# vic-20-mem-board.net
KiCad netlist of a schematic drawn in EAGLE
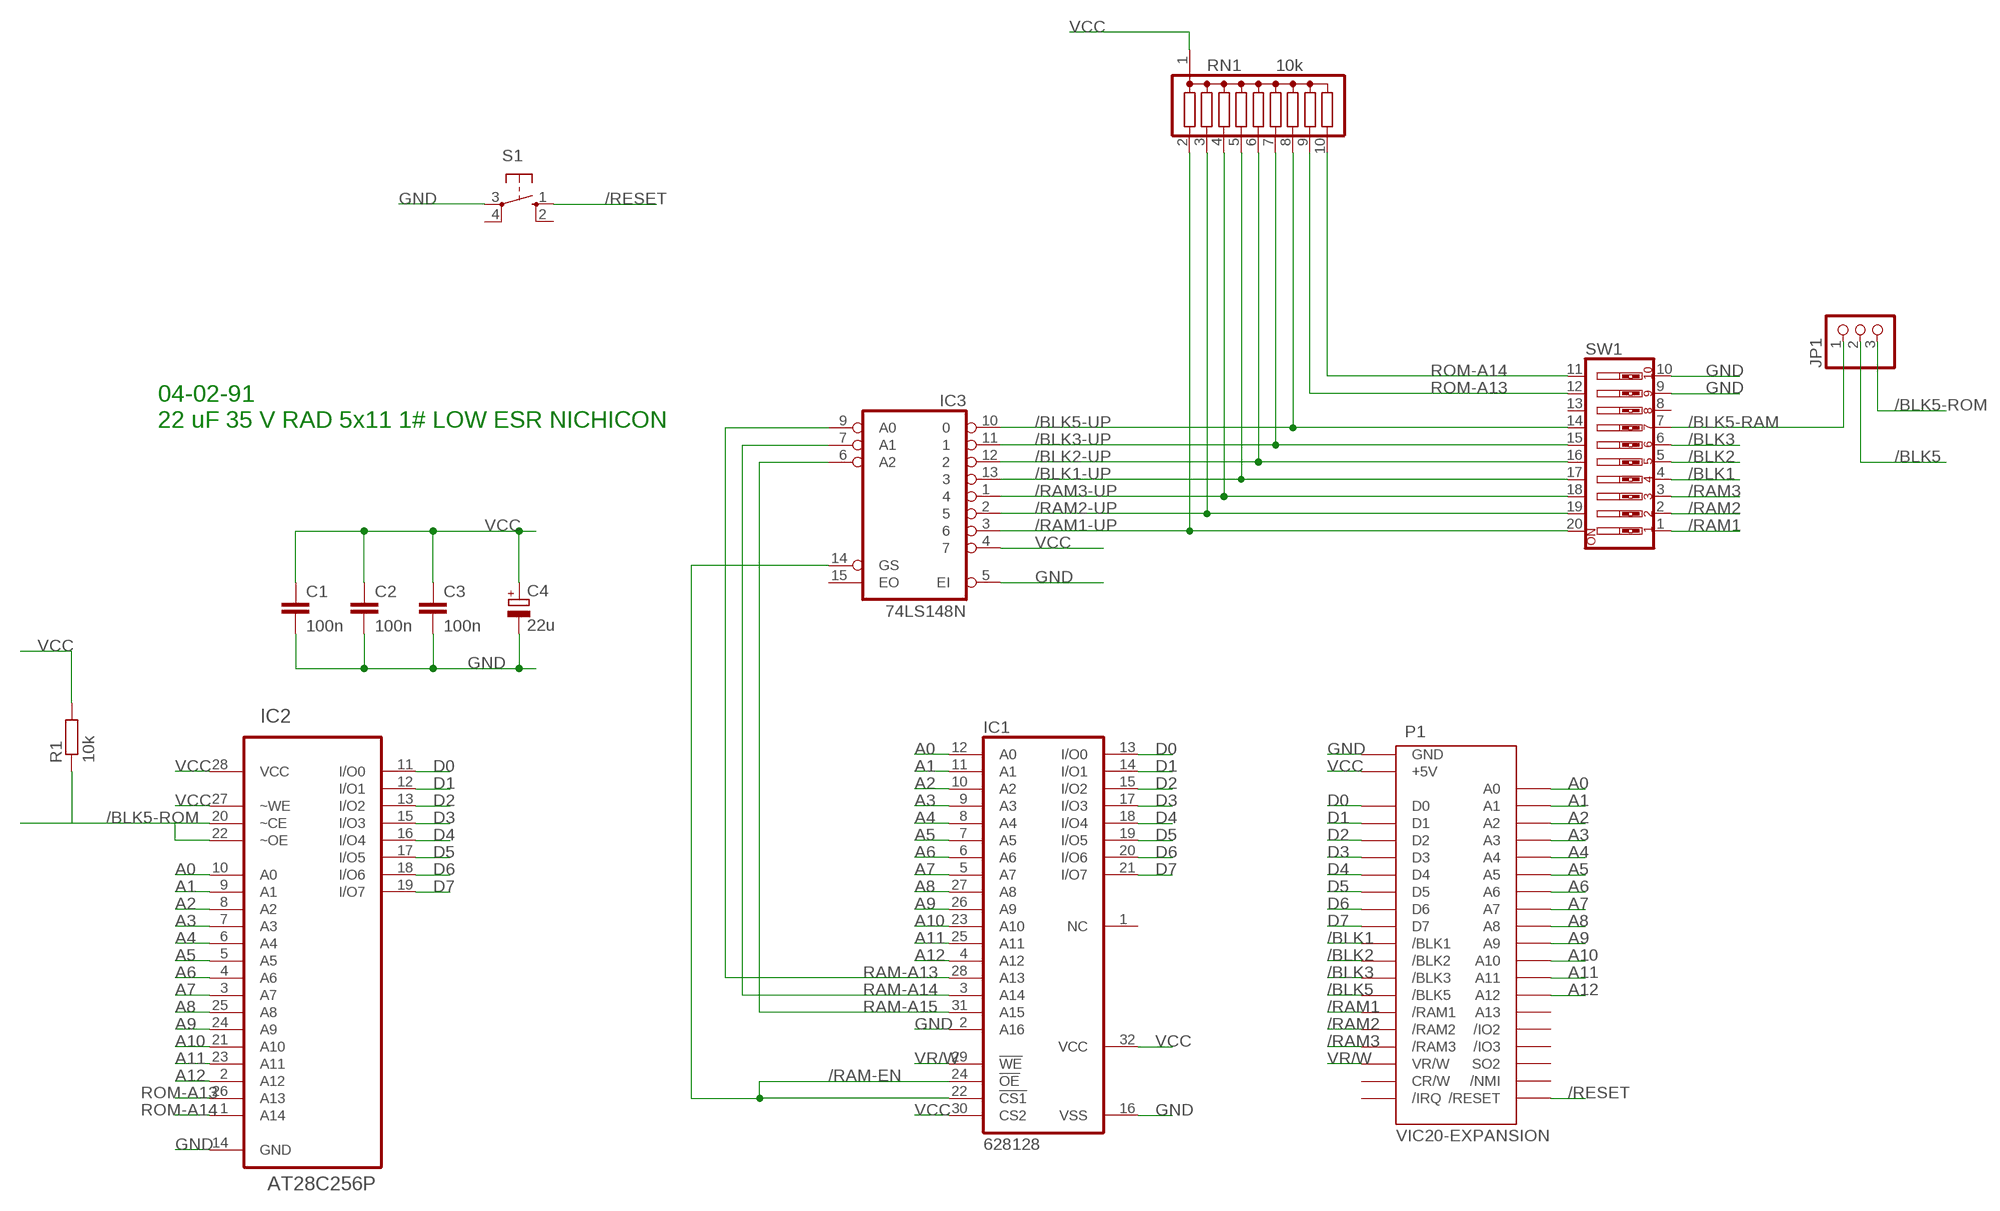
[diagram p0: schematic, sheet 1]

(export (version "E")
  (design (tool "Eeschema 10.0.6"))
  (components
    (comp (ref "C1")
      (value "100n")
      (footprint "eagle-import:C025-025X050")
      (libsource (lib "eagle-import") (part "C-EU025-025X050"))
    )
    (comp (ref "C2")
      (value "100n")
      (footprint "eagle-import:C025-025X050")
      (libsource (lib "eagle-import") (part "C-EU025-025X050"))
    )
    (comp (ref "C3")
      (value "100n")
      (footprint "eagle-import:C025-025X050")
      (libsource (lib "eagle-import") (part "C-EU025-025X050"))
    )
    (comp (ref "C4")
      (value "22u")
      (footprint "eagle-import:E2,5-5")
      (libsource (lib "eagle-import") (part "CPOL-EUE2.5-5"))
    )
    (comp (ref "IC1")
      (value "628128")
      (footprint "eagle-import:DIL32")
      (libsource (lib "eagle-import") (part "628128P"))
    )
    (comp (ref "IC2")
      (value "AT28C256P")
      (footprint "eagle-import:DIL28-6")
      (libsource (lib "eagle-import") (part "AT28C256P"))
    )
    (comp (ref "IC3")
      (value "74LS148N")
      (footprint "eagle-import:DIL16")
      (libsource (lib "eagle-import") (part "74148NLS"))
    )
    (comp (ref "JP1")
      (value "PINHD-1X3")
      (footprint "eagle-import:1X03")
      (libsource (lib "eagle-import") (part "PINHD-1X3"))
    )
    (comp (ref "P1")
      (value "VIC20-EXPANSION")
      (footprint "eagle-import:44PINEDGE")
      (libsource (lib "eagle-import") (part "VIC20-EXPANSION"))
    )
    (comp (ref "R1")
      (value "10k")
      (footprint "eagle-import:0204_7")
      (libsource (lib "eagle-import") (part "R-EU_0204/7"))
    )
    (comp (ref "RN1")
      (value "10k")
      (footprint "eagle-import:SIL10")
      (libsource (lib "eagle-import") (part "G09R"))
    )
    (comp (ref "S1")
      (value "10-XX")
      (footprint "eagle-import:B3F-10XX")
      (fields (field (name "MPN") "B3F-1000"))
      (libsource (lib "eagle-import") (part "10-XX"))
    )
    (comp (ref "SW1")
      (value "SW_DIP-10")
      (footprint "eagle-import:EDG-10")
      (libsource (lib "eagle-import") (part "SW_DIP-10"))
    )
  )
  (nets
    (net (code "1") (name "/A0") (class "Default")
      (node (ref "IC1") (pin "12") (pinfunction "A0_12") (pintype "input"))
      (node (ref "IC2") (pin "10") (pinfunction "A0_10") (pintype "input"))
      (node (ref "P1") (pin "B") (pinfunction "A0_B") (pintype "passive"))
    )
    (net (code "2") (name "/A1") (class "Default")
      (node (ref "IC1") (pin "11") (pinfunction "A1_11") (pintype "input"))
      (node (ref "IC2") (pin "9") (pinfunction "A1_9") (pintype "input"))
      (node (ref "P1") (pin "C") (pinfunction "A1_C") (pintype "passive"))
    )
    (net (code "3") (name "/A2") (class "Default")
      (node (ref "IC1") (pin "10") (pinfunction "A2_10") (pintype "input"))
      (node (ref "IC2") (pin "8") (pinfunction "A2_8") (pintype "input"))
      (node (ref "P1") (pin "D") (pinfunction "A2_D") (pintype "passive"))
    )
    (net (code "4") (name "/A3") (class "Default")
      (node (ref "IC1") (pin "9") (pinfunction "A3_9") (pintype "input"))
      (node (ref "IC2") (pin "7") (pinfunction "A3_7") (pintype "input"))
      (node (ref "P1") (pin "E") (pinfunction "A3_E") (pintype "passive"))
    )
    (net (code "5") (name "/A4") (class "Default")
      (node (ref "IC1") (pin "8") (pinfunction "A4_8") (pintype "input"))
      (node (ref "IC2") (pin "6") (pinfunction "A4_6") (pintype "input"))
      (node (ref "P1") (pin "F") (pinfunction "A4_F") (pintype "passive"))
    )
    (net (code "6") (name "/A5") (class "Default")
      (node (ref "IC1") (pin "7") (pinfunction "A5_7") (pintype "input"))
      (node (ref "IC2") (pin "5") (pinfunction "A5_5") (pintype "input"))
      (node (ref "P1") (pin "H") (pinfunction "A5_H") (pintype "passive"))
    )
    (net (code "7") (name "/A6") (class "Default")
      (node (ref "IC1") (pin "6") (pinfunction "A6_6") (pintype "input"))
      (node (ref "IC2") (pin "4") (pinfunction "A6_4") (pintype "input"))
      (node (ref "P1") (pin "J") (pinfunction "A6_J") (pintype "passive"))
    )
    (net (code "8") (name "/A7") (class "Default")
      (node (ref "IC1") (pin "5") (pinfunction "A7_5") (pintype "input"))
      (node (ref "IC2") (pin "3") (pinfunction "A7_3") (pintype "input"))
      (node (ref "P1") (pin "K") (pinfunction "A7_K") (pintype "passive"))
    )
    (net (code "9") (name "/A8") (class "Default")
      (node (ref "IC1") (pin "27") (pinfunction "A8_27") (pintype "input"))
      (node (ref "IC2") (pin "25") (pinfunction "A8_25") (pintype "input"))
      (node (ref "P1") (pin "L") (pinfunction "A8_L") (pintype "passive"))
    )
    (net (code "10") (name "/A9") (class "Default")
      (node (ref "IC1") (pin "26") (pinfunction "A9_26") (pintype "input"))
      (node (ref "IC2") (pin "24") (pinfunction "A9_24") (pintype "input"))
      (node (ref "P1") (pin "M") (pinfunction "A9_M") (pintype "passive"))
    )
    (net (code "11") (name "/A10") (class "Default")
      (node (ref "IC1") (pin "23") (pinfunction "A10_23") (pintype "input"))
      (node (ref "IC2") (pin "21") (pinfunction "A10_21") (pintype "input"))
      (node (ref "P1") (pin "N") (pinfunction "A10_N") (pintype "passive"))
    )
    (net (code "12") (name "/A11") (class "Default")
      (node (ref "IC1") (pin "25") (pinfunction "A11_25") (pintype "input"))
      (node (ref "IC2") (pin "23") (pinfunction "A11_23") (pintype "input"))
      (node (ref "P1") (pin "P") (pinfunction "A11_P") (pintype "passive"))
    )
    (net (code "13") (name "/A12") (class "Default")
      (node (ref "IC1") (pin "4") (pinfunction "A12_4") (pintype "input"))
      (node (ref "IC2") (pin "2") (pinfunction "A12_2") (pintype "input"))
      (node (ref "P1") (pin "R") (pinfunction "A12_R") (pintype "passive"))
    )
    (net (code "14") (name "/D0") (class "Default")
      (node (ref "IC1") (pin "13") (pinfunction "I/O0_13") (pintype "bidirectional"))
      (node (ref "IC2") (pin "11") (pinfunction "I/O0_11") (pintype "bidirectional"))
      (node (ref "P1") (pin "2") (pinfunction "D0_2") (pintype "passive"))
    )
    (net (code "15") (name "/D1") (class "Default")
      (node (ref "IC1") (pin "14") (pinfunction "I/O1_14") (pintype "bidirectional"))
      (node (ref "IC2") (pin "12") (pinfunction "I/O1_12") (pintype "bidirectional"))
      (node (ref "P1") (pin "3") (pinfunction "D1_3") (pintype "passive"))
    )
    (net (code "16") (name "/D2") (class "Default")
      (node (ref "IC1") (pin "15") (pinfunction "I/O2_15") (pintype "bidirectional"))
      (node (ref "IC2") (pin "13") (pinfunction "I/O2_13") (pintype "bidirectional"))
      (node (ref "P1") (pin "4") (pinfunction "D2_4") (pintype "passive"))
    )
    (net (code "17") (name "/D3") (class "Default")
      (node (ref "IC1") (pin "17") (pinfunction "I/O3_17") (pintype "bidirectional"))
      (node (ref "IC2") (pin "15") (pinfunction "I/O3_15") (pintype "bidirectional"))
      (node (ref "P1") (pin "5") (pinfunction "D3_5") (pintype "passive"))
    )
    (net (code "18") (name "/D4") (class "Default")
      (node (ref "IC1") (pin "18") (pinfunction "I/O4_18") (pintype "bidirectional"))
      (node (ref "IC2") (pin "16") (pinfunction "I/O4_16") (pintype "bidirectional"))
      (node (ref "P1") (pin "6") (pinfunction "D4_6") (pintype "passive"))
    )
    (net (code "19") (name "/D5") (class "Default")
      (node (ref "IC1") (pin "19") (pinfunction "I/O5_19") (pintype "bidirectional"))
      (node (ref "IC2") (pin "17") (pinfunction "I/O5_17") (pintype "bidirectional"))
      (node (ref "P1") (pin "7") (pinfunction "D5_7") (pintype "passive"))
    )
    (net (code "20") (name "/D6") (class "Default")
      (node (ref "IC1") (pin "20") (pinfunction "I/O6_20") (pintype "bidirectional"))
      (node (ref "IC2") (pin "18") (pinfunction "I/O6_18") (pintype "bidirectional"))
      (node (ref "P1") (pin "8") (pinfunction "D6_8") (pintype "passive"))
    )
    (net (code "21") (name "/D7") (class "Default")
      (node (ref "IC1") (pin "21") (pinfunction "I/O7_21") (pintype "bidirectional"))
      (node (ref "IC2") (pin "19") (pinfunction "I/O7_19") (pintype "bidirectional"))
      (node (ref "P1") (pin "9") (pinfunction "D7_9") (pintype "passive"))
    )
    (net (code "22") (name "/GND") (class "Default")
      (node (ref "C1") (pin "2") (pinfunction "2_2") (pintype "passive"))
      (node (ref "C2") (pin "2") (pinfunction "2_2") (pintype "passive"))
      (node (ref "C3") (pin "2") (pinfunction "2_2") (pintype "passive"))
      (node (ref "C4") (pin "-") (pinfunction "-_-") (pintype "passive"))
      (node (ref "IC1") (pin "16") (pinfunction "VSS_16") (pintype "power_in"))
      (node (ref "IC1") (pin "2") (pinfunction "A16_2") (pintype "input"))
      (node (ref "IC2") (pin "14") (pinfunction "GND_14") (pintype "passive"))
      (node (ref "IC3") (pin "5") (pinfunction "EI_5") (pintype "input"))
      (node (ref "P1") (pin "1") (pinfunction "GND_1") (pintype "passive"))
      (node (ref "P1") (pin "22") (pinfunction "GND_22") (pintype "passive"))
      (node (ref "P1") (pin "A") (pinfunction "GND_A") (pintype "passive"))
      (node (ref "P1") (pin "Z") (pinfunction "GND_Z") (pintype "passive"))
      (node (ref "S1") (pin "3") (pinfunction "P_3") (pintype "passive"))
      (node (ref "SW1") (pin "10") (pinfunction "10_10") (pintype "passive"))
      (node (ref "SW1") (pin "9") (pinfunction "9_9") (pintype "passive"))
    )
    (net (code "23") (name "/RAM-A13") (class "Default")
      (node (ref "IC1") (pin "28") (pinfunction "A13_28") (pintype "input"))
      (node (ref "IC3") (pin "9") (pinfunction "A0_9") (pintype "output"))
    )
    (net (code "24") (name "/RAM-A14") (class "Default")
      (node (ref "IC1") (pin "3") (pinfunction "A14_3") (pintype "input"))
      (node (ref "IC3") (pin "7") (pinfunction "A1_7") (pintype "output"))
    )
    (net (code "25") (name "/RAM-A15") (class "Default")
      (node (ref "IC1") (pin "31") (pinfunction "A15_31") (pintype "input"))
      (node (ref "IC3") (pin "6") (pinfunction "A2_6") (pintype "output"))
    )
    (net (code "26") (name "/ROM-A13") (class "Default")
      (node (ref "IC2") (pin "26") (pinfunction "A13_26") (pintype "input"))
      (node (ref "RN1") (pin "9") (pinfunction "9_9") (pintype "passive"))
      (node (ref "SW1") (pin "12") (pinfunction "12_12") (pintype "passive"))
    )
    (net (code "27") (name "/ROM-A14") (class "Default")
      (node (ref "IC2") (pin "1") (pinfunction "A14_1") (pintype "input"))
      (node (ref "RN1") (pin "10") (pinfunction "10_10") (pintype "passive"))
      (node (ref "SW1") (pin "11") (pinfunction "11_11") (pintype "passive"))
    )
    (net (code "28") (name "/VCC") (class "Default")
      (node (ref "C1") (pin "1") (pinfunction "1_1") (pintype "passive"))
      (node (ref "C2") (pin "1") (pinfunction "1_1") (pintype "passive"))
      (node (ref "C3") (pin "1") (pinfunction "1_1") (pintype "passive"))
      (node (ref "C4") (pin "+") (pinfunction "+_+") (pintype "passive"))
      (node (ref "IC1") (pin "30") (pinfunction "CS2_30") (pintype "input"))
      (node (ref "IC1") (pin "32") (pinfunction "VCC_32") (pintype "power_in"))
      (node (ref "IC2") (pin "27") (pinfunction "~{WE}_27") (pintype "input"))
      (node (ref "IC2") (pin "28") (pinfunction "VCC_28") (pintype "power_in"))
      (node (ref "IC3") (pin "4") (pinfunction "7_4") (pintype "input"))
      (node (ref "P1") (pin "21") (pinfunction "+5V_21") (pintype "passive"))
      (node (ref "R1") (pin "2") (pinfunction "2_2") (pintype "passive"))
      (node (ref "RN1") (pin "1") (pinfunction "1_1") (pintype "passive"))
    )
    (net (code "29") (name "/VR{slash}W") (class "Default")
      (node (ref "IC1") (pin "29") (pinfunction "~{WE}_29") (pintype "input"))
      (node (ref "P1") (pin "17") (pinfunction "VR/W_17") (pintype "passive"))
    )
    (net (code "30") (name "/{slash}BLK1") (class "Default")
      (node (ref "P1") (pin "10") (pinfunction "/BLK1_10") (pintype "passive"))
      (node (ref "SW1") (pin "4") (pinfunction "4_4") (pintype "passive"))
    )
    (net (code "31") (name "/{slash}BLK1-UP") (class "Default")
      (node (ref "IC3") (pin "13") (pinfunction "3_13") (pintype "input"))
      (node (ref "RN1") (pin "5") (pinfunction "5_5") (pintype "passive"))
      (node (ref "SW1") (pin "17") (pinfunction "17_17") (pintype "passive"))
    )
    (net (code "32") (name "/{slash}BLK2") (class "Default")
      (node (ref "P1") (pin "11") (pinfunction "/BLK2_11") (pintype "passive"))
      (node (ref "SW1") (pin "5") (pinfunction "5_5") (pintype "passive"))
    )
    (net (code "33") (name "/{slash}BLK2-UP") (class "Default")
      (node (ref "IC3") (pin "12") (pinfunction "2_12") (pintype "input"))
      (node (ref "RN1") (pin "6") (pinfunction "6_6") (pintype "passive"))
      (node (ref "SW1") (pin "16") (pinfunction "16_16") (pintype "passive"))
    )
    (net (code "34") (name "/{slash}BLK3") (class "Default")
      (node (ref "P1") (pin "12") (pinfunction "/BLK3_12") (pintype "passive"))
      (node (ref "SW1") (pin "6") (pinfunction "6_6") (pintype "passive"))
    )
    (net (code "35") (name "/{slash}BLK3-UP") (class "Default")
      (node (ref "IC3") (pin "11") (pinfunction "1_11") (pintype "input"))
      (node (ref "RN1") (pin "7") (pinfunction "7_7") (pintype "passive"))
      (node (ref "SW1") (pin "15") (pinfunction "15_15") (pintype "passive"))
    )
    (net (code "36") (name "/{slash}BLK5") (class "Default")
      (node (ref "JP1") (pin "2") (pinfunction "2_2") (pintype "passive"))
      (node (ref "P1") (pin "13") (pinfunction "/BLK5_13") (pintype "passive"))
    )
    (net (code "37") (name "/{slash}BLK5-RAM") (class "Default")
      (node (ref "JP1") (pin "1") (pinfunction "1_1") (pintype "passive"))
      (node (ref "SW1") (pin "7") (pinfunction "7_7") (pintype "passive"))
    )
    (net (code "38") (name "/{slash}BLK5-ROM") (class "Default")
      (node (ref "IC2") (pin "20") (pinfunction "~{CE}_20") (pintype "input"))
      (node (ref "IC2") (pin "22") (pinfunction "~{OE}_22") (pintype "input"))
      (node (ref "JP1") (pin "3") (pinfunction "3_3") (pintype "passive"))
      (node (ref "R1") (pin "1") (pinfunction "1_1") (pintype "passive"))
    )
    (net (code "39") (name "/{slash}BLK5-UP") (class "Default")
      (node (ref "IC3") (pin "10") (pinfunction "0_10") (pintype "input"))
      (node (ref "RN1") (pin "8") (pinfunction "8_8") (pintype "passive"))
      (node (ref "SW1") (pin "14") (pinfunction "14_14") (pintype "passive"))
    )
    (net (code "40") (name "/{slash}RAM-EN") (class "Default")
      (node (ref "IC1") (pin "22") (pinfunction "~{CS1}_22") (pintype "input"))
      (node (ref "IC1") (pin "24") (pinfunction "~{OE}_24") (pintype "input"))
      (node (ref "IC3") (pin "14") (pinfunction "GS_14") (pintype "output"))
    )
    (net (code "41") (name "/{slash}RAM1") (class "Default")
      (node (ref "P1") (pin "14") (pinfunction "/RAM1_14") (pintype "passive"))
      (node (ref "SW1") (pin "1") (pinfunction "1_1") (pintype "passive"))
    )
    (net (code "42") (name "/{slash}RAM1-UP") (class "Default")
      (node (ref "IC3") (pin "3") (pinfunction "6_3") (pintype "input"))
      (node (ref "RN1") (pin "2") (pinfunction "2_2") (pintype "passive"))
      (node (ref "SW1") (pin "20") (pinfunction "20_20") (pintype "passive"))
    )
    (net (code "43") (name "/{slash}RAM2") (class "Default")
      (node (ref "P1") (pin "15") (pinfunction "/RAM2_15") (pintype "passive"))
      (node (ref "SW1") (pin "2") (pinfunction "2_2") (pintype "passive"))
    )
    (net (code "44") (name "/{slash}RAM2-UP") (class "Default")
      (node (ref "IC3") (pin "2") (pinfunction "5_2") (pintype "input"))
      (node (ref "RN1") (pin "3") (pinfunction "3_3") (pintype "passive"))
      (node (ref "SW1") (pin "19") (pinfunction "19_19") (pintype "passive"))
    )
    (net (code "45") (name "/{slash}RAM3") (class "Default")
      (node (ref "P1") (pin "16") (pinfunction "/RAM3_16") (pintype "passive"))
      (node (ref "SW1") (pin "3") (pinfunction "3_3") (pintype "passive"))
    )
    (net (code "46") (name "/{slash}RAM3-UP") (class "Default")
      (node (ref "IC3") (pin "1") (pinfunction "4_1") (pintype "input"))
      (node (ref "RN1") (pin "4") (pinfunction "4_4") (pintype "passive"))
      (node (ref "SW1") (pin "18") (pinfunction "18_18") (pintype "passive"))
    )
    (net (code "47") (name "/{slash}RESET") (class "Default")
      (node (ref "P1") (pin "X") (pinfunction "/RESET_X") (pintype "passive"))
      (node (ref "S1") (pin "1") (pinfunction "S_1") (pintype "passive"))
    )
    (net (code "48") (name "unconnected-(IC1-NC-Pad1)") (class "Default")
      (node (ref "IC1") (pin "1") (pinfunction "NC_1") (pintype "no_connect"))
    )
    (net (code "49") (name "unconnected-(IC3A-EO-Pad15)") (class "Default")
      (node (ref "IC3") (pin "15") (pinfunction "EO_15") (pintype "output"))
    )
    (net (code "50") (name "unconnected-(P1-A13-PadS)") (class "Default")
      (node (ref "P1") (pin "S") (pinfunction "A13_S") (pintype "passive"))
    )
    (net (code "51") (name "unconnected-(P1-CR{slash}W-Pad18)") (class "Default")
      (node (ref "P1") (pin "18") (pinfunction "CR/W_18") (pintype "passive"))
    )
    (net (code "52") (name "unconnected-(P1-SO2-PadV)") (class "Default")
      (node (ref "P1") (pin "V") (pinfunction "SO2_V") (pintype "passive"))
    )
    (net (code "53") (name "unconnected-(P1-{slash}IO2-PadT)") (class "Default")
      (node (ref "P1") (pin "T") (pinfunction "/IO2_T") (pintype "passive"))
    )
    (net (code "54") (name "unconnected-(P1-{slash}IO3-PadU)") (class "Default")
      (node (ref "P1") (pin "U") (pinfunction "/IO3_U") (pintype "passive"))
    )
    (net (code "55") (name "unconnected-(P1-{slash}IRQ-Pad19)") (class "Default")
      (node (ref "P1") (pin "19") (pinfunction "/IRQ_19") (pintype "passive"))
    )
    (net (code "56") (name "unconnected-(P1-{slash}NMI-PadW)") (class "Default")
      (node (ref "P1") (pin "W") (pinfunction "/NMI_W") (pintype "passive"))
    )
    (net (code "57") (name "unconnected-(S1-P1-Pad4)") (class "Default")
      (node (ref "S1") (pin "4") (pinfunction "P1_4") (pintype "passive"))
    )
    (net (code "58") (name "unconnected-(S1-S1-Pad2)") (class "Default")
      (node (ref "S1") (pin "2") (pinfunction "S1_2") (pintype "passive"))
    )
    (net (code "59") (name "unconnected-(SW1-Pad8)") (class "Default")
      (node (ref "SW1") (pin "8") (pinfunction "8_8") (pintype "passive"))
    )
    (net (code "60") (name "unconnected-(SW1-Pad13)") (class "Default")
      (node (ref "SW1") (pin "13") (pinfunction "13_13") (pintype "passive"))
    )
  )
)
